# CRSC0005.net
KiCad netlist of a schematic drawn in Altium Designer
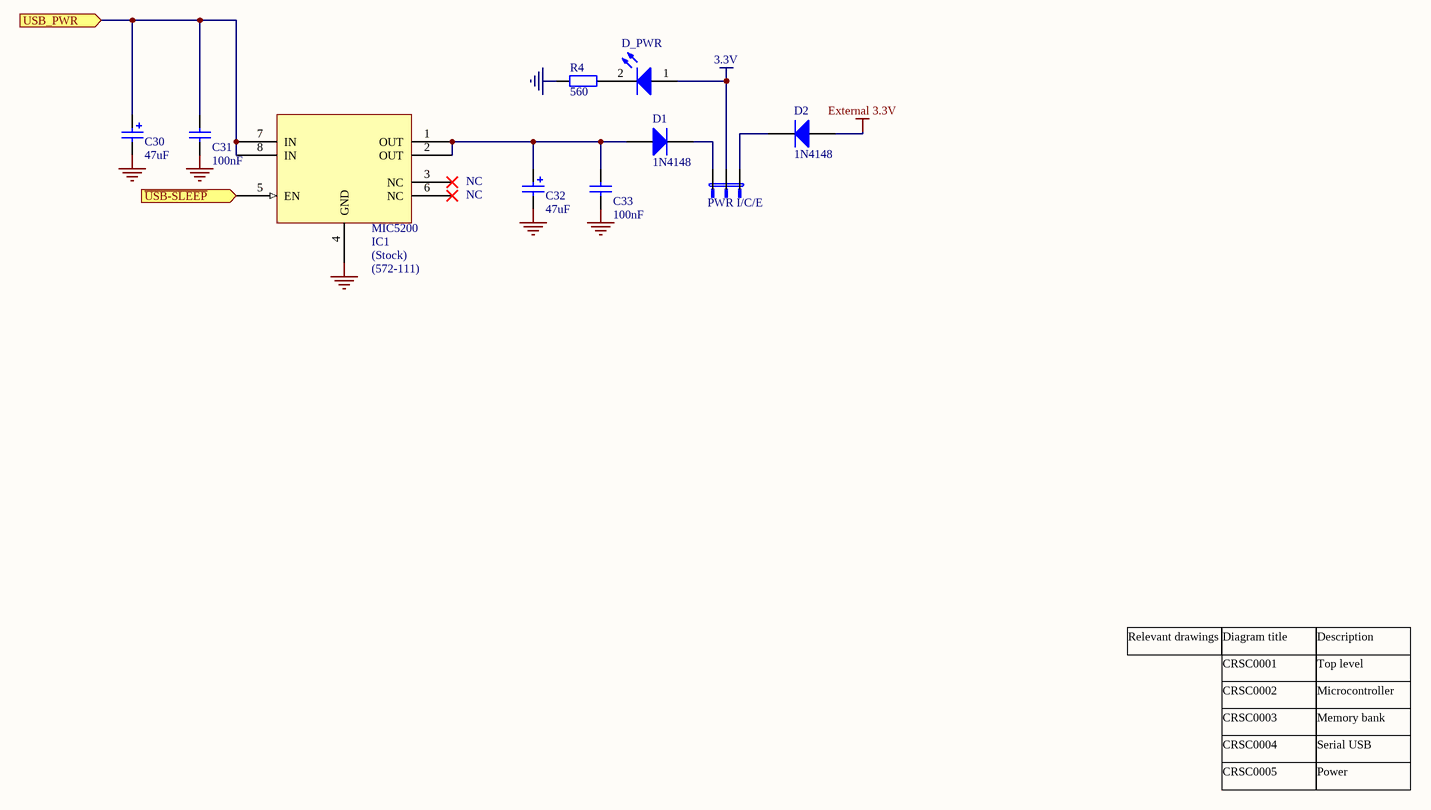
[diagram p0: CRSC0005.SchDoc]

(export (version "E")
  (design (tool "Eeschema 10.0.6"))
  (components
    (comp (ref "C30")
      (value "47uF")
      (footprint "SMDD_E")
      (description "Polarized Capacitor (Surface Mount)")
      (fields
        (field (name "MANUFACTURER") "Generic Components")
        (field (name "Comment") "Cap Pol3")
        (field (name "PUBLISHER") "Altium Hobart Technology Centre")
      )
      (libsource (lib "Miscellaneous Devices") (part "Cap Pol3"))
    )
    (comp (ref "C31")
      (value "100nF")
      (footprint "0805")
      (description "Capacitor (Semiconductor SIM Model)")
      (fields
        (field (name "MANUFACTURER") "Generic Components")
        (field (name "Comment") "Cap Semi")
        (field (name "PUBLISHER") "Altium Hobart Technology Centre")
      )
      (libsource (lib "Miscellaneous Devices") (part "Cap Semi"))
    )
    (comp (ref "C32")
      (value "47uF")
      (footprint "smdd_e")
      (description "Polarized Capacitor (Surface Mount)")
      (fields
        (field (name "MANUFACTURER") "Generic Components")
        (field (name "Comment") "Cap Pol3")
        (field (name "PUBLISHER") "Altium Hobart Technology Centre")
      )
      (libsource (lib "Miscellaneous Devices") (part "Cap Pol3"))
    )
    (comp (ref "C33")
      (value "100nF")
      (footprint "0805")
      (description "Capacitor (Semiconductor SIM Model)")
      (fields
        (field (name "MANUFACTURER") "Generic Components")
        (field (name "Comment") "Cap Semi")
        (field (name "PUBLISHER") "Altium Hobart Technology Centre")
      )
      (libsource (lib "Miscellaneous Devices") (part "Cap Semi"))
    )
    (comp (ref "D1")
      (value "1N4148")
      (footprint "SOD123")
      (description "High Conductance Fast Diode")
      (fields (field (name "PUBLISHER") "Altium Limited"))
      (libsource (lib "SELF-MADE_2905") (part "1N4148"))
    )
    (comp (ref "D2")
      (value "1N4148")
      (footprint "SOD123")
      (description "High Conductance Fast Diode")
      (fields (field (name "PUBLISHER") "Altium Limited"))
      (libsource (lib "SELF-MADE_2905") (part "1N4148"))
    )
    (comp (ref "D_PWR")
      (value "LED")
      (footprint "0805")
      (description "Typical INFRARED GaAs LED")
      (fields
        (field (name "MANUFACTURER") "Generic Components")
        (field (name "PUBLISHER") "Altium Hobart Technology Centre")
      )
      (libsource (lib "SELF-MADE_1004") (part "LED0"))
    )
    (comp (ref "IC1")
      (value "MIC5200")
      (footprint "MIC5200-3.3BM")
      (description "MIC5200-3.3BM 3.3V 100mA LDO Voltage Regulator")
      (libsource (lib "Components") (part "MIC5200"))
    )
    (comp (ref "PWR I/C/E")
      (value "3pins jumper")
      (footprint "JUMPER3pins")
      (libsource (lib "SELF-MADE_2905") (part "3pins jumper"))
    )
    (comp (ref "R4")
      (value "560")
      (footprint "0805")
      (description "Resistor")
      (fields
        (field (name "MANUFACTURER") "Generic Components")
        (field (name "PUBLISHER") "Altium Hobart Technology Centre")
      )
      (libsource (lib "SELF-MADE_1004") (part "Res2"))
    )
  )
  (nets
    (net (code "1") (name "/USB-SLEEP") (class "Default")
      (node (ref "IC1") (pin "5") (pinfunction "EN_5") (pintype "input"))
    )
    (net (code "2") (name "/USB_PWR") (class "Default")
      (node (ref "C30") (pin "1") (pinfunction "1_1") (pintype "passive"))
      (node (ref "C31") (pin "1") (pinfunction "1_1") (pintype "passive"))
      (node (ref "IC1") (pin "7") (pinfunction "IN_7") (pintype "power_in"))
      (node (ref "IC1") (pin "8") (pinfunction "IN_8") (pintype "power_in"))
    )
    (net (code "3") (name "3.3V") (class "Default")
      (node (ref "D_PWR") (pin "1") (pinfunction "A_1") (pintype "passive"))
      (node (ref "PWR I/C/E") (pin "2") (pinfunction "2_2") (pintype "passive"))
    )
    (net (code "4") (name "External 3.3V") (class "Default")
      (node (ref "D2") (pin "1") (pinfunction "A_1") (pintype "passive"))
    )
    (net (code "5") (name "GND") (class "Default")
      (node (ref "C30") (pin "2") (pinfunction "2_2") (pintype "passive"))
      (node (ref "C31") (pin "2") (pinfunction "2_2") (pintype "passive"))
      (node (ref "C32") (pin "2") (pinfunction "2_2") (pintype "passive"))
      (node (ref "C33") (pin "2") (pinfunction "2_2") (pintype "passive"))
      (node (ref "IC1") (pin "4") (pinfunction "GND_4") (pintype "power_in"))
      (node (ref "R4") (pin "1") (pinfunction "1_1") (pintype "passive"))
    )
    (net (code "6") (name "Net-(D1-A)") (class "Default")
      (node (ref "C32") (pin "1") (pinfunction "1_1") (pintype "passive"))
      (node (ref "C33") (pin "1") (pinfunction "1_1") (pintype "passive"))
      (node (ref "D1") (pin "1") (pinfunction "A_1") (pintype "passive"))
      (node (ref "IC1") (pin "1") (pinfunction "OUT_1") (pintype "power_in"))
      (node (ref "IC1") (pin "2") (pinfunction "OUT_2") (pintype "power_in"))
    )
    (net (code "7") (name "Net-(D1-K)") (class "Default")
      (node (ref "D1") (pin "2") (pinfunction "K_2") (pintype "passive"))
      (node (ref "PWR I/C/E") (pin "1") (pinfunction "1_1") (pintype "passive"))
    )
    (net (code "8") (name "Net-(D2-K)") (class "Default")
      (node (ref "D2") (pin "2") (pinfunction "K_2") (pintype "passive"))
      (node (ref "PWR I/C/E") (pin "3") (pinfunction "3_3") (pintype "passive"))
    )
    (net (code "9") (name "Net-(D_PWR-K)") (class "Default")
      (node (ref "D_PWR") (pin "2") (pinfunction "K_2") (pintype "passive"))
      (node (ref "R4") (pin "2") (pinfunction "2_2") (pintype "passive"))
    )
    (net (code "10") (name "unconnected-(IC1-NC-Pad3)") (class "Default")
      (node (ref "IC1") (pin "3") (pinfunction "NC_3") (pintype "passive+no_connect"))
    )
    (net (code "11") (name "unconnected-(IC1-NC-Pad6)") (class "Default")
      (node (ref "IC1") (pin "6") (pinfunction "NC_6") (pintype "passive+no_connect"))
    )
  )
)
